# BME680.net
KiCad netlist of a schematic drawn in Altium Designer
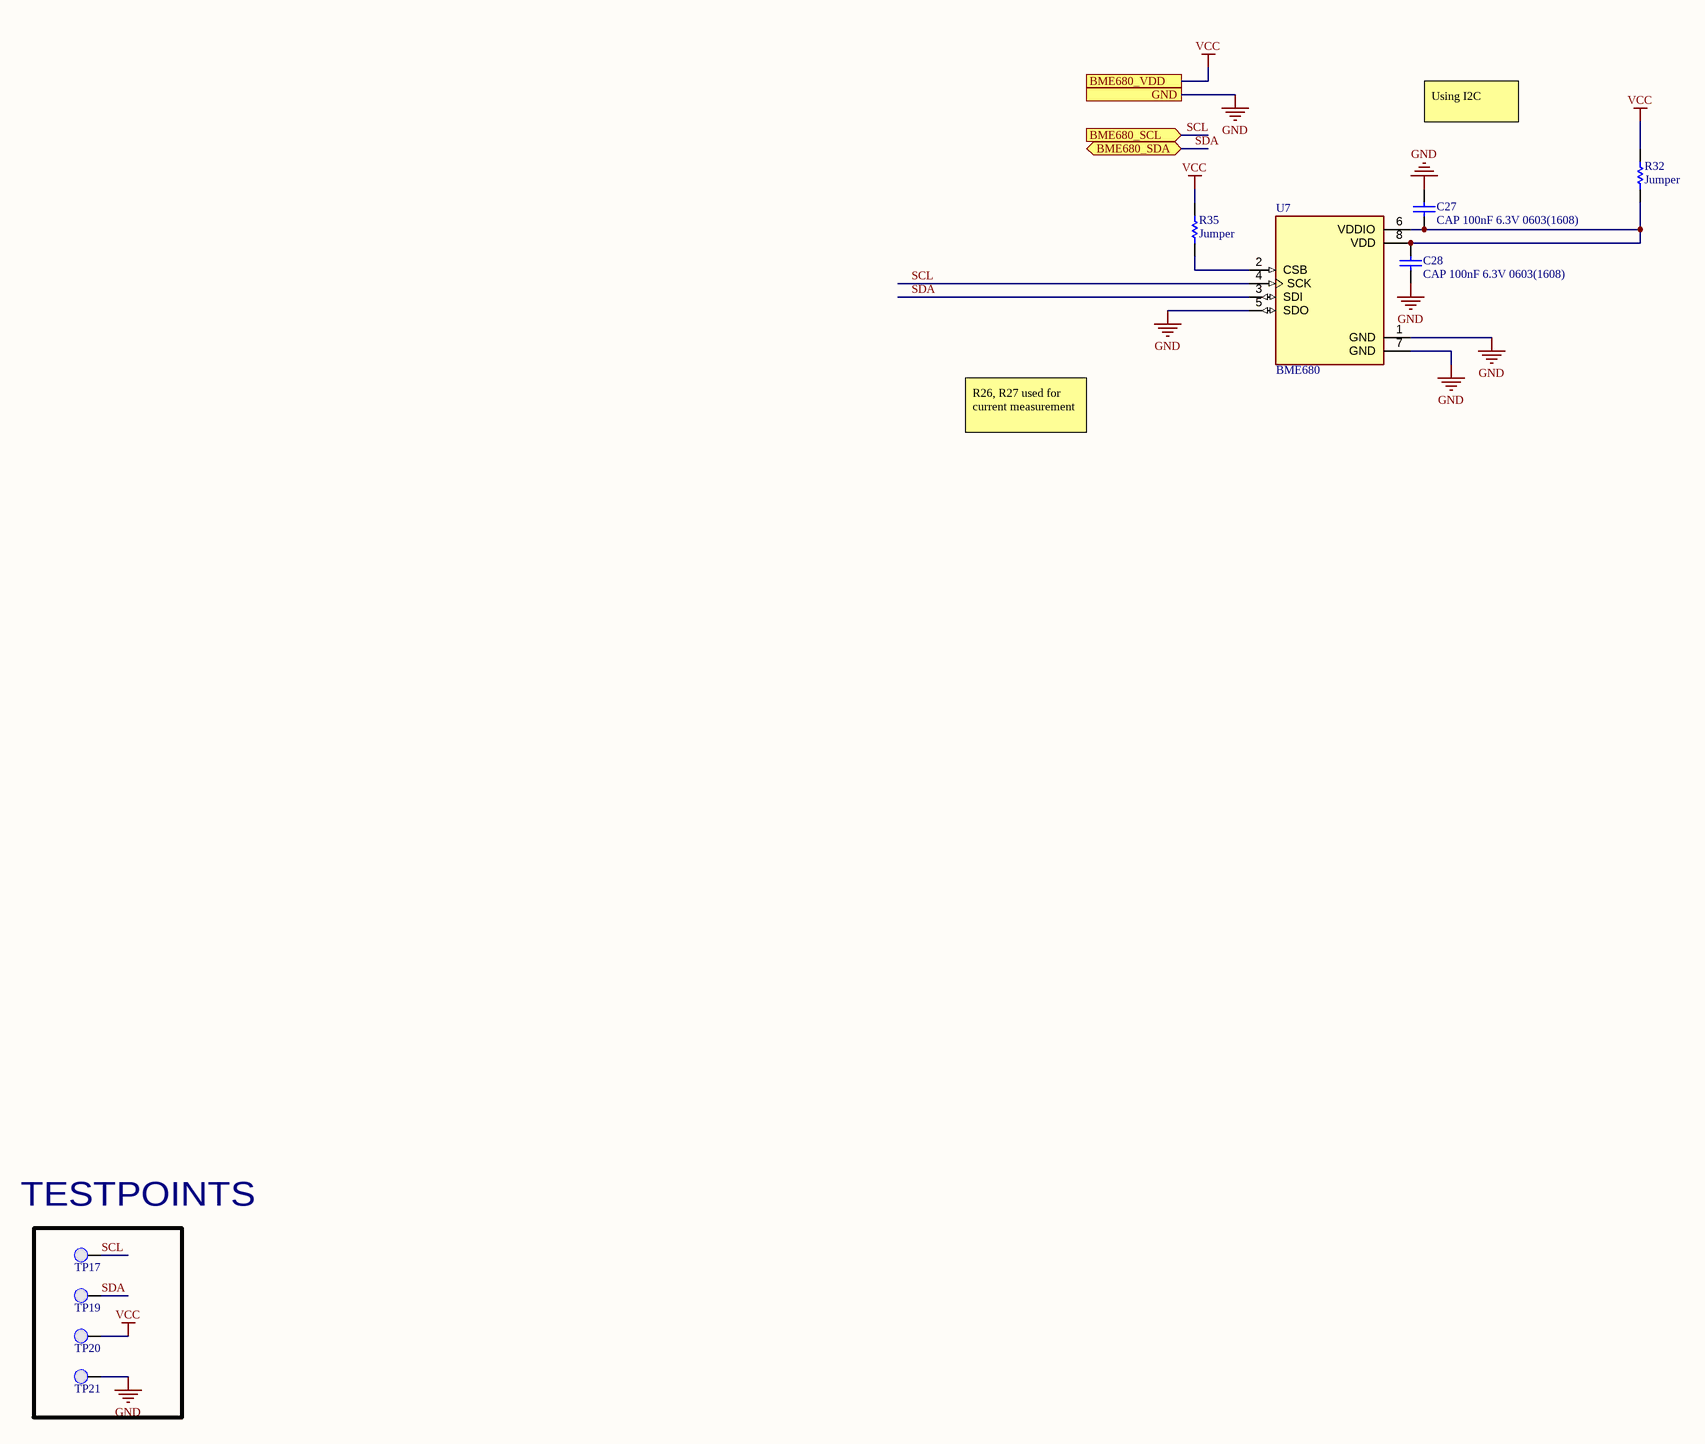
[diagram p0: BME680.SchDoc]

(export (version "E")
  (design (tool "Eeschema 10.0.6"))
  (components
    (comp (ref "C27")
      (value "CAP 100nF 6.3V 0603(1608)")
      (footprint "CAPC0603(1608)100_M")
      (description "CAP 100nF 6.3V ±5% 0603 (1608 Metric) Thickness 1mm SMD")
      (fields (field (name "TOLERANCE") "Â±5%"))
      (libsource (lib "Altium Content Vault") (part "CAP"))
    )
    (comp (ref "C28")
      (value "CAP 100nF 6.3V 0603(1608)")
      (footprint "CAPC0603(1608)100_M")
      (description "CAP 100nF 6.3V ±5% 0603 (1608 Metric) Thickness 1mm SMD")
      (fields (field (name "TOLERANCE") "Â±5%"))
      (libsource (lib "Altium Content Vault") (part "CAP"))
    )
    (comp (ref "R32")
      (value "Jumper")
      (footprint "RESC0603(1608)_N")
      (description "Jumper 0603 (1608 Metric)")
      (fields (field (name "POWER") "None"))
      (libsource (lib "Altium Content Vault") (part "RES"))
    )
    (comp (ref "R35")
      (value "Jumper")
      (footprint "RESC0603(1608)_N")
      (description "Jumper 0603 (1608 Metric)")
      (fields (field (name "POWER") "None"))
      (libsource (lib "Altium Content Vault") (part "RES"))
    )
    (comp (ref "TP17")
      (value "0.1\" Pad")
      (footprint "PCBComponent")
      (libsource (lib "Components - 12.02.20 - 18.05") (part "0.1{dblquote} Pad-A.4"))
    )
    (comp (ref "TP19")
      (value "0.1\" Pad")
      (footprint "PCBComponent")
      (libsource (lib "Components - 12.02.20 - 18.05") (part "0.1{dblquote} Pad-A.4"))
    )
    (comp (ref "TP20")
      (value "0.1\" Pad")
      (footprint "PCBComponent")
      (libsource (lib "Components - 12.02.20 - 18.05") (part "0.1{dblquote} Pad-A.4"))
    )
    (comp (ref "TP21")
      (value "0.1\" Pad")
      (footprint "PCBComponent")
      (libsource (lib "Components - 12.02.20 - 18.05") (part "0.1{dblquote} Pad-A.4"))
    )
    (comp (ref "U7")
      (value "BME680")
      (footprint "PSON80P300X300X100-8N")
      (description "Integrated Environmental Unit")
      (fields (field (name "MF") "{'manufacturer': u'Bosch Sensortec'}"))
      (libsource (lib "SnapEDA_Library") (part "BME680"))
    )
  )
  (nets
    (net (code "1") (name "/SCL") (class "Default")
      (node (ref "TP17") (pin "1") (pinfunction "PAD_1") (pintype "passive"))
      (node (ref "U7") (pin "4") (pinfunction "SCK_4") (pintype "input"))
    )
    (net (code "2") (name "/SDA") (class "Default")
      (node (ref "TP19") (pin "1") (pinfunction "PAD_1") (pintype "passive"))
      (node (ref "U7") (pin "3") (pinfunction "SDI_3") (pintype "bidirectional"))
    )
    (net (code "3") (name "GND") (class "Default")
      (node (ref "C27") (pin "1") (pinfunction "1_1") (pintype "passive"))
      (node (ref "C28") (pin "1") (pinfunction "1_1") (pintype "passive"))
      (node (ref "TP21") (pin "1") (pinfunction "PAD_1") (pintype "passive"))
      (node (ref "U7") (pin "1") (pinfunction "GND_1") (pintype "power_in"))
      (node (ref "U7") (pin "5") (pinfunction "SDO_5") (pintype "bidirectional"))
      (node (ref "U7") (pin "7") (pinfunction "GND_7") (pintype "power_in"))
    )
    (net (code "4") (name "Net-(U7-CSB)") (class "Default")
      (node (ref "R35") (pin "1") (pinfunction "1_1") (pintype "passive"))
      (node (ref "U7") (pin "2") (pinfunction "CSB_2") (pintype "input"))
    )
    (net (code "5") (name "Net-(U7-VDD)") (class "Default")
      (node (ref "C27") (pin "2") (pinfunction "2_2") (pintype "passive"))
      (node (ref "C28") (pin "2") (pinfunction "2_2") (pintype "passive"))
      (node (ref "R32") (pin "1") (pinfunction "1_1") (pintype "passive"))
      (node (ref "U7") (pin "6") (pinfunction "VDDIO_6") (pintype "power_in"))
      (node (ref "U7") (pin "8") (pinfunction "VDD_8") (pintype "power_in"))
    )
    (net (code "6") (name "VCC") (class "Default")
      (node (ref "R32") (pin "2") (pinfunction "2_2") (pintype "passive"))
      (node (ref "R35") (pin "2") (pinfunction "2_2") (pintype "passive"))
      (node (ref "TP20") (pin "1") (pinfunction "PAD_1") (pintype "passive"))
    )
  )
)
